# LEDRing.net
KiCad netlist of a schematic drawn in EAGLE
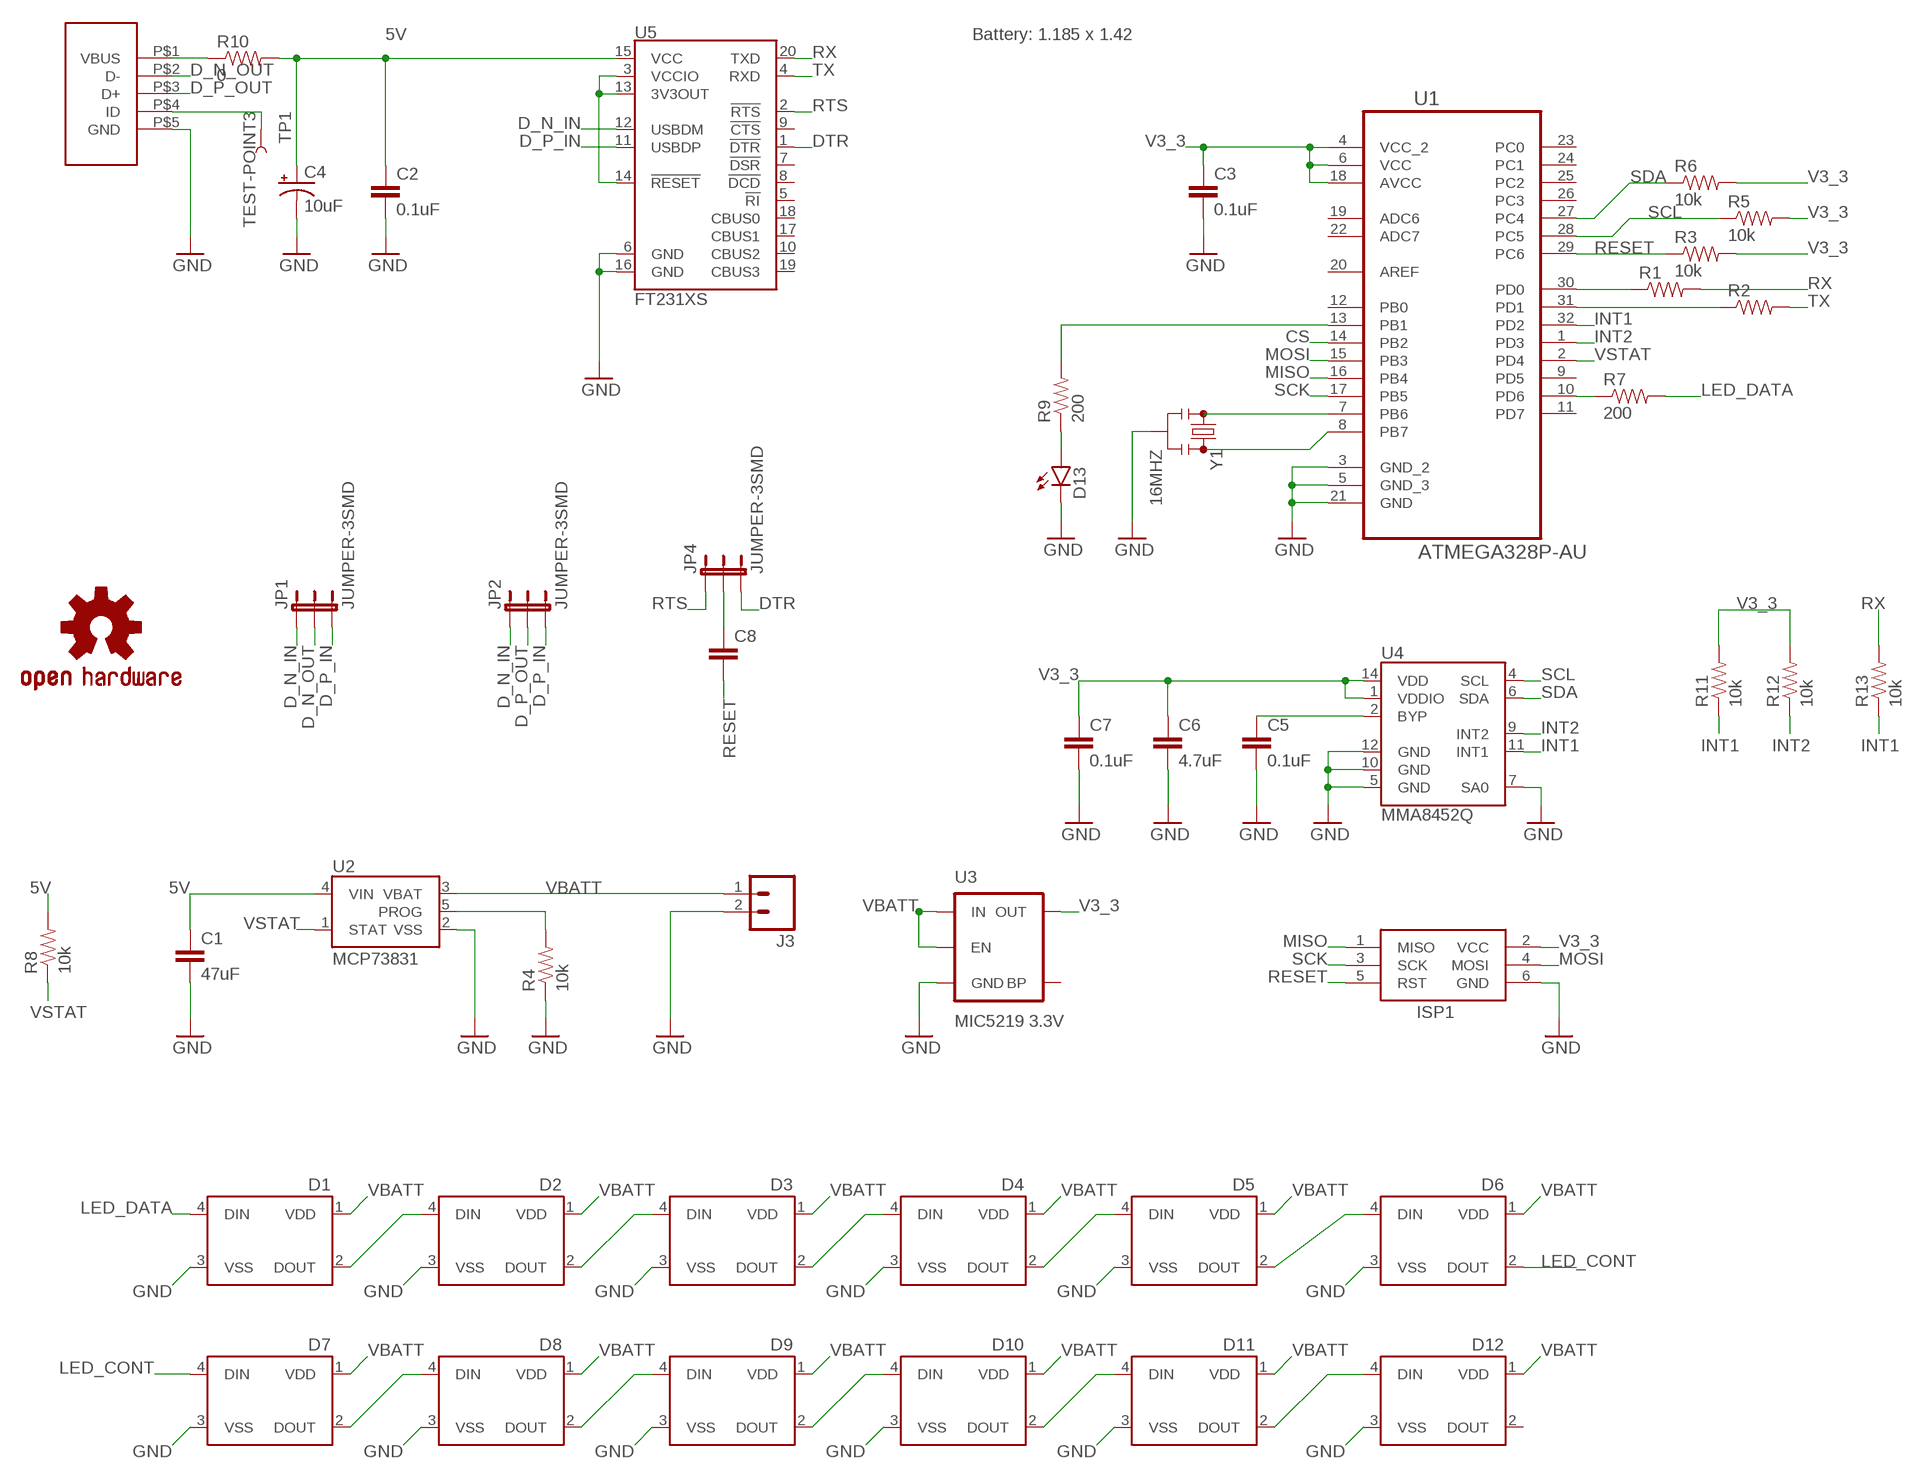
[diagram p0: schematic, sheet 1, part 1 of 2]
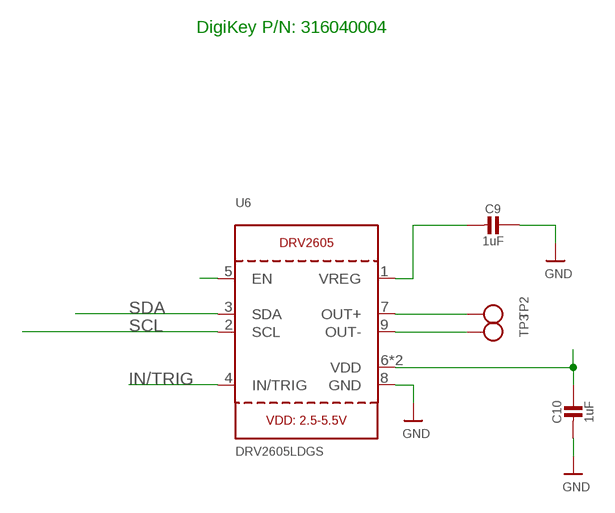
[diagram p1: schematic, sheet 1, part 2 of 2]

(export (version "E")
  (design (tool "Eeschema 10.0.6"))
  (components
    (comp (ref "C1")
      (value "47uF")
      (footprint "eagle-import:0603-CAP")
      (libsource (lib "eagle-import") (part "CAP0603-CAP"))
    )
    (comp (ref "C2")
      (value "0.1uF")
      (footprint "eagle-import:0603-CAP")
      (libsource (lib "eagle-import") (part "CAP0603-CAP"))
    )
    (comp (ref "C3")
      (value "0.1uF")
      (footprint "eagle-import:0603-CAP")
      (libsource (lib "eagle-import") (part "CAP0603-CAP"))
    )
    (comp (ref "C4")
      (value "10uF")
      (footprint "eagle-import:0603-POL")
      (libsource (lib "eagle-import") (part "10UF-6.3V-20%(0603)(TANT){dblquote}"))
    )
    (comp (ref "C5")
      (value "0.1uF")
      (footprint "eagle-import:0603-CAP")
      (libsource (lib "eagle-import") (part "CAP0603-CAP"))
    )
    (comp (ref "C6")
      (value "4.7uF")
      (footprint "eagle-import:0603-CAP")
      (libsource (lib "eagle-import") (part "CAP0603-CAP"))
    )
    (comp (ref "C7")
      (value "0.1uF")
      (footprint "eagle-import:0603-CAP")
      (libsource (lib "eagle-import") (part "CAP0603-CAP"))
    )
    (comp (ref "C8")
      (value "CAP0603-CAP")
      (footprint "eagle-import:0603-CAP")
      (libsource (lib "eagle-import") (part "CAP0603-CAP"))
    )
    (comp (ref "C9")
      (value "1uF")
      (footprint "eagle-import:0805-NO")
      (libsource (lib "eagle-import") (part "CAP_CERAMIC0805-NOOUTLINE"))
    )
    (comp (ref "C10")
      (value "1uF")
      (footprint "eagle-import:0805-NO")
      (libsource (lib "eagle-import") (part "CAP_CERAMIC0805-NOOUTLINE"))
    )
    (comp (ref "D1")
      (value "WS2812B")
      (footprint "eagle-import:WS2812B")
      (libsource (lib "eagle-import") (part "WS2812B"))
    )
    (comp (ref "D2")
      (value "WS2812B")
      (footprint "eagle-import:WS2812B")
      (libsource (lib "eagle-import") (part "WS2812B"))
    )
    (comp (ref "D3")
      (value "WS2812B")
      (footprint "eagle-import:WS2812B")
      (libsource (lib "eagle-import") (part "WS2812B"))
    )
    (comp (ref "D4")
      (value "WS2812B")
      (footprint "eagle-import:WS2812B")
      (libsource (lib "eagle-import") (part "WS2812B"))
    )
    (comp (ref "D5")
      (value "WS2812B")
      (footprint "eagle-import:WS2812B")
      (libsource (lib "eagle-import") (part "WS2812B"))
    )
    (comp (ref "D6")
      (value "WS2812B")
      (footprint "eagle-import:WS2812B")
      (libsource (lib "eagle-import") (part "WS2812B"))
    )
    (comp (ref "D7")
      (value "WS2812B")
      (footprint "eagle-import:WS2812B")
      (libsource (lib "eagle-import") (part "WS2812B"))
    )
    (comp (ref "D8")
      (value "WS2812B")
      (footprint "eagle-import:WS2812B")
      (libsource (lib "eagle-import") (part "WS2812B"))
    )
    (comp (ref "D9")
      (value "WS2812B")
      (footprint "eagle-import:WS2812B")
      (libsource (lib "eagle-import") (part "WS2812B"))
    )
    (comp (ref "D10")
      (value "WS2812B")
      (footprint "eagle-import:WS2812B")
      (libsource (lib "eagle-import") (part "WS2812B"))
    )
    (comp (ref "D11")
      (value "WS2812B")
      (footprint "eagle-import:WS2812B")
      (libsource (lib "eagle-import") (part "WS2812B"))
    )
    (comp (ref "D12")
      (value "WS2812B")
      (footprint "eagle-import:WS2812B")
      (libsource (lib "eagle-import") (part "WS2812B"))
    )
    (comp (ref "D13")
      (value "LED0603")
      (footprint "eagle-import:LED-0603")
      (libsource (lib "eagle-import") (part "LED0603"))
    )
    (comp (ref "ISP1")
      (value "AVRISP-BOX")
      (footprint "eagle-import:AVRISP-BOX")
      (libsource (lib "eagle-import") (part "AVRISP-BOX"))
    )
    (comp (ref "J3")
      (value "M02PTH")
      (footprint "eagle-import:1X02")
      (libsource (lib "eagle-import") (part "M02PTH"))
    )
    (comp (ref "JP1")
      (value "JUMPER-3SMD")
      (footprint "eagle-import:SJ_3")
      (libsource (lib "eagle-import") (part "JUMPER-3SMD"))
    )
    (comp (ref "JP2")
      (value "JUMPER-3SMD")
      (footprint "eagle-import:SJ_3")
      (libsource (lib "eagle-import") (part "JUMPER-3SMD"))
    )
    (comp (ref "JP4")
      (value "JUMPER-3SMD")
      (footprint "eagle-import:SJ_3")
      (libsource (lib "eagle-import") (part "JUMPER-3SMD"))
    )
    (comp (ref "LOGO1")
      (value "OSHW-LOGOMINI")
      (footprint "eagle-import:OSHW-LOGO-MINI")
      (libsource (lib "eagle-import") (part "OSHW-LOGOMINI"))
    )
    (comp (ref "R1")
      (value "RESISTOR0603-RES")
      (footprint "eagle-import:0603-RES")
      (libsource (lib "eagle-import") (part "RESISTOR0603-RES"))
    )
    (comp (ref "R2")
      (value "RESISTOR0603-RES")
      (footprint "eagle-import:0603-RES")
      (libsource (lib "eagle-import") (part "RESISTOR0603-RES"))
    )
    (comp (ref "R3")
      (value "10k")
      (footprint "eagle-import:0603-RES")
      (libsource (lib "eagle-import") (part "RESISTOR0603-RES"))
    )
    (comp (ref "R4")
      (value "10k")
      (footprint "eagle-import:0603-RES")
      (libsource (lib "eagle-import") (part "RESISTOR0603-RES"))
    )
    (comp (ref "R5")
      (value "10k")
      (footprint "eagle-import:0603-RES")
      (libsource (lib "eagle-import") (part "RESISTOR0603-RES"))
    )
    (comp (ref "R6")
      (value "10k")
      (footprint "eagle-import:0603-RES")
      (libsource (lib "eagle-import") (part "RESISTOR0603-RES"))
    )
    (comp (ref "R7")
      (value "200")
      (footprint "eagle-import:0603-RES")
      (libsource (lib "eagle-import") (part "RESISTOR0603-RES"))
    )
    (comp (ref "R8")
      (value "10k")
      (footprint "eagle-import:0603-RES")
      (libsource (lib "eagle-import") (part "RESISTOR0603-RES"))
    )
    (comp (ref "R9")
      (value "200")
      (footprint "eagle-import:0603-RES")
      (libsource (lib "eagle-import") (part "RESISTOR0603-RES"))
    )
    (comp (ref "R10")
      (value "0")
      (footprint "eagle-import:0603-RES")
      (libsource (lib "eagle-import") (part "RESISTOR0603-RES"))
    )
    (comp (ref "R11")
      (value "10k")
      (footprint "eagle-import:0603-RES")
      (libsource (lib "eagle-import") (part "RESISTOR0603-RES"))
    )
    (comp (ref "R12")
      (value "10k")
      (footprint "eagle-import:0603-RES")
      (libsource (lib "eagle-import") (part "RESISTOR0603-RES"))
    )
    (comp (ref "R13")
      (value "10k")
      (footprint "eagle-import:0603-RES")
      (libsource (lib "eagle-import") (part "RESISTOR0603-RES"))
    )
    (comp (ref "TP1")
      (value "TEST-POINT3")
      (footprint "eagle-import:PAD.03X.03")
      (libsource (lib "eagle-import") (part "TEST-POINT3"))
    )
    (comp (ref "TP2")
      (value "TESTPOINTPAD2MM")
      (footprint "eagle-import:TESTPOINT_PAD_2MM")
      (libsource (lib "eagle-import") (part "TESTPOINTPAD2MM"))
    )
    (comp (ref "TP3")
      (value "TESTPOINTPAD2MM")
      (footprint "eagle-import:TESTPOINT_PAD_2MM")
      (libsource (lib "eagle-import") (part "TESTPOINTPAD2MM"))
    )
    (comp (ref "U$1")
      (value "TE_USB_A121025CT")
      (footprint "eagle-import:TE_USB_A121025CT")
      (libsource (lib "eagle-import") (part "TE_USB_A121025CT"))
    )
    (comp (ref "U1")
      (value "ATMEGA328P-AU")
      (footprint "eagle-import:QFP80P900X900X120-32N")
      (libsource (lib "eagle-import") (part "ATMEGA328P-AU"))
    )
    (comp (ref "U2")
      (value "MCP73831")
      (footprint "eagle-import:SOT23-5")
      (libsource (lib "eagle-import") (part "MCP73831"))
    )
    (comp (ref "U3")
      (value "MIC5219 3.3V")
      (footprint "eagle-import:SOT23-5")
      (libsource (lib "eagle-import") (part "V_REG_MIC52193.3V"))
    )
    (comp (ref "U4")
      (value "MMA8452Q")
      (footprint "eagle-import:QFN-16_0.5MM")
      (libsource (lib "eagle-import") (part "MMA8452Q"))
    )
    (comp (ref "U5")
      (value "FT231XS")
      (footprint "eagle-import:SSOP20_L")
      (libsource (lib "eagle-import") (part "FT231XS"))
    )
    (comp (ref "U6")
      (value "DRV2605LDGS")
      (footprint "eagle-import:PSOP10")
      (libsource (lib "eagle-import") (part "DRV2605_SOP"))
    )
    (comp (ref "Y1")
      (value "16MHZ")
      (footprint "eagle-import:RESONATOR-SMD")
      (libsource (lib "eagle-import") (part "RESONATOR16MHZ"))
    )
  )
  (nets
    (net (code "1") (name "/5V") (class "Default")
      (node (ref "C1") (pin "1") (pinfunction "1_1") (pintype "passive"))
      (node (ref "C2") (pin "1") (pinfunction "1_1") (pintype "passive"))
      (node (ref "C4") (pin "A") (pinfunction "+_A") (pintype "passive"))
      (node (ref "R10") (pin "2") (pinfunction "2_2") (pintype "passive"))
      (node (ref "R8") (pin "2") (pinfunction "2_2") (pintype "passive"))
      (node (ref "U2") (pin "4") (pinfunction "VIN_4") (pintype "power_in"))
      (node (ref "U5") (pin "15") (pinfunction "VCC_15") (pintype "bidirectional"))
    )
    (net (code "2") (name "/CS") (class "Default")
      (node (ref "U1") (pin "14") (pinfunction "PB2_14") (pintype "bidirectional"))
    )
    (net (code "3") (name "/DTR") (class "Default")
      (node (ref "JP4") (pin "3") (pinfunction "3_3") (pintype "passive"))
      (node (ref "U5") (pin "1") (pinfunction "~{DTR}_1") (pintype "bidirectional"))
    )
    (net (code "4") (name "/D_N_IN") (class "Default")
      (node (ref "JP1") (pin "1") (pinfunction "1_1") (pintype "passive"))
      (node (ref "JP2") (pin "1") (pinfunction "1_1") (pintype "passive"))
      (node (ref "U5") (pin "12") (pinfunction "USBDM_12") (pintype "bidirectional"))
    )
    (net (code "5") (name "/D_N_OUT") (class "Default")
      (node (ref "JP1") (pin "2") (pinfunction "2_2") (pintype "passive"))
      (node (ref "U$1") (pin "P$2") (pinfunction "D-_P$2") (pintype "bidirectional"))
    )
    (net (code "6") (name "/D_P_IN") (class "Default")
      (node (ref "JP1") (pin "3") (pinfunction "3_3") (pintype "passive"))
      (node (ref "JP2") (pin "3") (pinfunction "3_3") (pintype "passive"))
      (node (ref "U5") (pin "11") (pinfunction "USBDP_11") (pintype "bidirectional"))
    )
    (net (code "7") (name "/D_P_OUT") (class "Default")
      (node (ref "JP2") (pin "2") (pinfunction "2_2") (pintype "passive"))
      (node (ref "U$1") (pin "P$3") (pinfunction "D+_P$3") (pintype "bidirectional"))
    )
    (net (code "8") (name "/INT1") (class "Default")
      (node (ref "R11") (pin "1") (pinfunction "1_1") (pintype "passive"))
      (node (ref "R13") (pin "1") (pinfunction "1_1") (pintype "passive"))
      (node (ref "U1") (pin "32") (pinfunction "PD2_32") (pintype "bidirectional"))
      (node (ref "U4") (pin "11") (pinfunction "INT1_11") (pintype "bidirectional"))
    )
    (net (code "9") (name "/INT2") (class "Default")
      (node (ref "R12") (pin "1") (pinfunction "1_1") (pintype "passive"))
      (node (ref "U1") (pin "1") (pinfunction "PD3_1") (pintype "bidirectional"))
      (node (ref "U4") (pin "9") (pinfunction "INT2_9") (pintype "bidirectional"))
    )
    (net (code "10") (name "/IN{slash}TRIG") (class "Default")
      (node (ref "U6") (pin "4") (pinfunction "IN/TRIG_4") (pintype "input"))
    )
    (net (code "11") (name "/LED_CONT") (class "Default")
      (node (ref "D6") (pin "2") (pinfunction "DOUT_2") (pintype "output"))
      (node (ref "D7") (pin "4") (pinfunction "DIN_4") (pintype "input"))
    )
    (net (code "12") (name "/LED_DATA") (class "Default")
      (node (ref "D1") (pin "4") (pinfunction "DIN_4") (pintype "input"))
      (node (ref "R7") (pin "2") (pinfunction "2_2") (pintype "passive"))
    )
    (net (code "13") (name "/MISO") (class "Default")
      (node (ref "ISP1") (pin "1") (pinfunction "MISO_1") (pintype "input"))
      (node (ref "U1") (pin "16") (pinfunction "PB4_16") (pintype "bidirectional"))
    )
    (net (code "14") (name "/MOSI") (class "Default")
      (node (ref "ISP1") (pin "4") (pinfunction "MOSI_4") (pintype "output"))
      (node (ref "U1") (pin "15") (pinfunction "PB3_15") (pintype "bidirectional"))
    )
    (net (code "15") (name "/RESET") (class "Default")
      (node (ref "C8") (pin "2") (pinfunction "2_2") (pintype "passive"))
      (node (ref "ISP1") (pin "5") (pinfunction "RST_5") (pintype "output"))
      (node (ref "R3") (pin "1") (pinfunction "1_1") (pintype "passive"))
      (node (ref "U1") (pin "29") (pinfunction "PC6_29") (pintype "bidirectional"))
    )
    (net (code "16") (name "/RTS") (class "Default")
      (node (ref "JP4") (pin "1") (pinfunction "1_1") (pintype "passive"))
      (node (ref "U5") (pin "2") (pinfunction "~{RTS}_2") (pintype "bidirectional"))
    )
    (net (code "17") (name "/RX") (class "Default")
      (node (ref "R1") (pin "2") (pinfunction "2_2") (pintype "passive"))
      (node (ref "R13") (pin "2") (pinfunction "2_2") (pintype "passive"))
      (node (ref "U5") (pin "20") (pinfunction "TXD_20") (pintype "bidirectional"))
    )
    (net (code "18") (name "/SCK") (class "Default")
      (node (ref "ISP1") (pin "3") (pinfunction "SCK_3") (pintype "output"))
      (node (ref "U1") (pin "17") (pinfunction "PB5_17") (pintype "bidirectional"))
    )
    (net (code "19") (name "/SCL") (class "Default")
      (node (ref "R5") (pin "1") (pinfunction "1_1") (pintype "passive"))
      (node (ref "U1") (pin "28") (pinfunction "PC5_28") (pintype "bidirectional"))
      (node (ref "U4") (pin "4") (pinfunction "SCL_4") (pintype "bidirectional"))
      (node (ref "U6") (pin "2") (pinfunction "SCL_2") (pintype "input"))
    )
    (net (code "20") (name "/SDA") (class "Default")
      (node (ref "R6") (pin "1") (pinfunction "1_1") (pintype "passive"))
      (node (ref "U1") (pin "27") (pinfunction "PC4_27") (pintype "bidirectional"))
      (node (ref "U4") (pin "6") (pinfunction "SDA_6") (pintype "bidirectional"))
      (node (ref "U6") (pin "3") (pinfunction "SDA_3") (pintype "bidirectional"))
    )
    (net (code "21") (name "/TX") (class "Default")
      (node (ref "R2") (pin "2") (pinfunction "2_2") (pintype "passive"))
      (node (ref "U5") (pin "4") (pinfunction "RXD_4") (pintype "bidirectional"))
    )
    (net (code "22") (name "/V3_3") (class "Default")
      (node (ref "C3") (pin "1") (pinfunction "1_1") (pintype "passive"))
      (node (ref "C6") (pin "1") (pinfunction "1_1") (pintype "passive"))
      (node (ref "C7") (pin "1") (pinfunction "1_1") (pintype "passive"))
      (node (ref "ISP1") (pin "2") (pinfunction "VCC_2") (pintype "power_in"))
      (node (ref "R11") (pin "2") (pinfunction "2_2") (pintype "passive"))
      (node (ref "R12") (pin "2") (pinfunction "2_2") (pintype "passive"))
      (node (ref "R3") (pin "2") (pinfunction "2_2") (pintype "passive"))
      (node (ref "R5") (pin "2") (pinfunction "2_2") (pintype "passive"))
      (node (ref "R6") (pin "2") (pinfunction "2_2") (pintype "passive"))
      (node (ref "U1") (pin "18") (pinfunction "AVCC_18") (pintype "power_in"))
      (node (ref "U1") (pin "4") (pinfunction "VCC_2_4") (pintype "power_in"))
      (node (ref "U1") (pin "6") (pinfunction "VCC_6") (pintype "power_in"))
      (node (ref "U3") (pin "5") (pinfunction "OUT_5") (pintype "passive"))
      (node (ref "U4") (pin "1") (pinfunction "VDDIO_1") (pintype "bidirectional"))
      (node (ref "U4") (pin "14") (pinfunction "VDD_14") (pintype "bidirectional"))
    )
    (net (code "23") (name "/VBATT") (class "Default")
      (node (ref "D1") (pin "1") (pinfunction "VDD_1") (pintype "power_in"))
      (node (ref "D10") (pin "1") (pinfunction "VDD_1") (pintype "power_in"))
      (node (ref "D11") (pin "1") (pinfunction "VDD_1") (pintype "power_in"))
      (node (ref "D12") (pin "1") (pinfunction "VDD_1") (pintype "power_in"))
      (node (ref "D2") (pin "1") (pinfunction "VDD_1") (pintype "power_in"))
      (node (ref "D3") (pin "1") (pinfunction "VDD_1") (pintype "power_in"))
      (node (ref "D4") (pin "1") (pinfunction "VDD_1") (pintype "power_in"))
      (node (ref "D5") (pin "1") (pinfunction "VDD_1") (pintype "power_in"))
      (node (ref "D6") (pin "1") (pinfunction "VDD_1") (pintype "power_in"))
      (node (ref "D7") (pin "1") (pinfunction "VDD_1") (pintype "power_in"))
      (node (ref "D8") (pin "1") (pinfunction "VDD_1") (pintype "power_in"))
      (node (ref "D9") (pin "1") (pinfunction "VDD_1") (pintype "power_in"))
      (node (ref "J3") (pin "1") (pinfunction "1_1") (pintype "passive"))
      (node (ref "U2") (pin "3") (pinfunction "VBAT_3") (pintype "power_in"))
      (node (ref "U3") (pin "1") (pinfunction "IN_1") (pintype "input"))
      (node (ref "U3") (pin "3") (pinfunction "EN_3") (pintype "input"))
    )
    (net (code "24") (name "/VSTAT") (class "Default")
      (node (ref "R8") (pin "1") (pinfunction "1_1") (pintype "passive"))
      (node (ref "U1") (pin "2") (pinfunction "PD4_2") (pintype "bidirectional"))
      (node (ref "U2") (pin "1") (pinfunction "STAT_1") (pintype "output"))
    )
    (net (code "25") (name "GND") (class "Default")
      (node (ref "C1") (pin "2") (pinfunction "2_2") (pintype "passive"))
      (node (ref "C10") (pin "2") (pinfunction "2_2") (pintype "passive"))
      (node (ref "C2") (pin "2") (pinfunction "2_2") (pintype "passive"))
      (node (ref "C3") (pin "2") (pinfunction "2_2") (pintype "passive"))
      (node (ref "C4") (pin "K") (pinfunction "-_K") (pintype "passive"))
      (node (ref "C5") (pin "2") (pinfunction "2_2") (pintype "passive"))
      (node (ref "C6") (pin "2") (pinfunction "2_2") (pintype "passive"))
      (node (ref "C7") (pin "2") (pinfunction "2_2") (pintype "passive"))
      (node (ref "C9") (pin "1") (pinfunction "1_1") (pintype "passive"))
      (node (ref "D1") (pin "3") (pinfunction "VSS_3") (pintype "power_in"))
      (node (ref "D10") (pin "3") (pinfunction "VSS_3") (pintype "power_in"))
      (node (ref "D11") (pin "3") (pinfunction "VSS_3") (pintype "power_in"))
      (node (ref "D12") (pin "3") (pinfunction "VSS_3") (pintype "power_in"))
      (node (ref "D13") (pin "C") (pinfunction "C_C") (pintype "passive"))
      (node (ref "D2") (pin "3") (pinfunction "VSS_3") (pintype "power_in"))
      (node (ref "D3") (pin "3") (pinfunction "VSS_3") (pintype "power_in"))
      (node (ref "D4") (pin "3") (pinfunction "VSS_3") (pintype "power_in"))
      (node (ref "D5") (pin "3") (pinfunction "VSS_3") (pintype "power_in"))
      (node (ref "D6") (pin "3") (pinfunction "VSS_3") (pintype "power_in"))
      (node (ref "D7") (pin "3") (pinfunction "VSS_3") (pintype "power_in"))
      (node (ref "D8") (pin "3") (pinfunction "VSS_3") (pintype "power_in"))
      (node (ref "D9") (pin "3") (pinfunction "VSS_3") (pintype "power_in"))
      (node (ref "ISP1") (pin "6") (pinfunction "GND_6") (pintype "power_in"))
      (node (ref "J3") (pin "2") (pinfunction "2_2") (pintype "passive"))
      (node (ref "R4") (pin "1") (pinfunction "1_1") (pintype "passive"))
      (node (ref "U$1") (pin "P$5") (pinfunction "GND_P$5") (pintype "bidirectional"))
      (node (ref "U1") (pin "21") (pinfunction "GND_21") (pintype "passive"))
      (node (ref "U1") (pin "3") (pinfunction "GND_2_3") (pintype "passive"))
      (node (ref "U1") (pin "5") (pinfunction "GND_3_5") (pintype "passive"))
      (node (ref "U2") (pin "2") (pinfunction "VSS_2") (pintype "power_in"))
      (node (ref "U3") (pin "2") (pinfunction "GND_2") (pintype "input"))
      (node (ref "U4") (pin "10") (pinfunction "GND_10") (pintype "bidirectional"))
      (node (ref "U4") (pin "12") (pinfunction "GND_12") (pintype "bidirectional"))
      (node (ref "U4") (pin "5") (pinfunction "GND_5") (pintype "bidirectional"))
      (node (ref "U4") (pin "7") (pinfunction "SA0_7") (pintype "bidirectional"))
      (node (ref "U5") (pin "16") (pinfunction "GND_16") (pintype "bidirectional"))
      (node (ref "U5") (pin "6") (pinfunction "GND_6") (pintype "bidirectional"))
      (node (ref "U6") (pin "8") (pinfunction "GND_8") (pintype "power_in"))
      (node (ref "Y1") (pin "2") (pinfunction "2_2") (pintype "passive"))
    )
    (net (code "26") (name "Net-(C8-Pad1)") (class "Default")
      (node (ref "C8") (pin "1") (pinfunction "1_1") (pintype "passive"))
      (node (ref "JP4") (pin "2") (pinfunction "2_2") (pintype "passive"))
    )
    (net (code "27") (name "Net-(C10-Pad1)") (class "Default")
      (node (ref "C10") (pin "1") (pinfunction "1_1") (pintype "passive"))
      (node (ref "U6") (pin "10") (pinfunction "VDD_10") (pintype "power_in"))
      (node (ref "U6") (pin "6") (pinfunction "VDD_6") (pintype "power_in"))
    )
    (net (code "28") (name "Net-(D1-DOUT)") (class "Default")
      (node (ref "D1") (pin "2") (pinfunction "DOUT_2") (pintype "output"))
      (node (ref "D2") (pin "4") (pinfunction "DIN_4") (pintype "input"))
    )
    (net (code "29") (name "Net-(D2-DOUT)") (class "Default")
      (node (ref "D2") (pin "2") (pinfunction "DOUT_2") (pintype "output"))
      (node (ref "D3") (pin "4") (pinfunction "DIN_4") (pintype "input"))
    )
    (net (code "30") (name "Net-(D3-DOUT)") (class "Default")
      (node (ref "D3") (pin "2") (pinfunction "DOUT_2") (pintype "output"))
      (node (ref "D4") (pin "4") (pinfunction "DIN_4") (pintype "input"))
    )
    (net (code "31") (name "Net-(D4-DOUT)") (class "Default")
      (node (ref "D4") (pin "2") (pinfunction "DOUT_2") (pintype "output"))
      (node (ref "D5") (pin "4") (pinfunction "DIN_4") (pintype "input"))
    )
    (net (code "32") (name "Net-(D5-DOUT)") (class "Default")
      (node (ref "D5") (pin "2") (pinfunction "DOUT_2") (pintype "output"))
      (node (ref "D6") (pin "4") (pinfunction "DIN_4") (pintype "input"))
    )
    (net (code "33") (name "Net-(D7-DOUT)") (class "Default")
      (node (ref "D7") (pin "2") (pinfunction "DOUT_2") (pintype "output"))
      (node (ref "D8") (pin "4") (pinfunction "DIN_4") (pintype "input"))
    )
    (net (code "34") (name "Net-(D8-DOUT)") (class "Default")
      (node (ref "D8") (pin "2") (pinfunction "DOUT_2") (pintype "output"))
      (node (ref "D9") (pin "4") (pinfunction "DIN_4") (pintype "input"))
    )
    (net (code "35") (name "Net-(D10-DIN)") (class "Default")
      (node (ref "D10") (pin "4") (pinfunction "DIN_4") (pintype "input"))
      (node (ref "D9") (pin "2") (pinfunction "DOUT_2") (pintype "output"))
    )
    (net (code "36") (name "Net-(D10-DOUT)") (class "Default")
      (node (ref "D10") (pin "2") (pinfunction "DOUT_2") (pintype "output"))
      (node (ref "D11") (pin "4") (pinfunction "DIN_4") (pintype "input"))
    )
    (net (code "37") (name "Net-(D11-DOUT)") (class "Default")
      (node (ref "D11") (pin "2") (pinfunction "DOUT_2") (pintype "output"))
      (node (ref "D12") (pin "4") (pinfunction "DIN_4") (pintype "input"))
    )
    (net (code "38") (name "Net-(D13-PadA)") (class "Default")
      (node (ref "D13") (pin "A") (pinfunction "A_A") (pintype "passive"))
      (node (ref "R9") (pin "1") (pinfunction "1_1") (pintype "passive"))
    )
    (net (code "39") (name "Net-(TP1-1)") (class "Default")
      (node (ref "TP1") (pin "P$1") (pinfunction "1_P$1") (pintype "bidirectional"))
      (node (ref "U$1") (pin "P$4") (pinfunction "ID_P$4") (pintype "bidirectional"))
    )
    (net (code "40") (name "Net-(U$1-VBUS)") (class "Default")
      (node (ref "R10") (pin "1") (pinfunction "1_1") (pintype "passive"))
      (node (ref "U$1") (pin "P$1") (pinfunction "VBUS_P$1") (pintype "bidirectional"))
    )
    (net (code "41") (name "Net-(U1-PB1)") (class "Default")
      (node (ref "R9") (pin "2") (pinfunction "2_2") (pintype "passive"))
      (node (ref "U1") (pin "13") (pinfunction "PB1_13") (pintype "bidirectional"))
    )
    (net (code "42") (name "Net-(U1-PB6)") (class "Default")
      (node (ref "U1") (pin "7") (pinfunction "PB6_7") (pintype "bidirectional"))
      (node (ref "Y1") (pin "1") (pinfunction "1_1") (pintype "passive"))
    )
    (net (code "43") (name "Net-(U1-PB7)") (class "Default")
      (node (ref "U1") (pin "8") (pinfunction "PB7_8") (pintype "bidirectional"))
      (node (ref "Y1") (pin "3") (pinfunction "3_3") (pintype "passive"))
    )
    (net (code "44") (name "Net-(U1-PD0)") (class "Default")
      (node (ref "R1") (pin "1") (pinfunction "1_1") (pintype "passive"))
      (node (ref "U1") (pin "30") (pinfunction "PD0_30") (pintype "bidirectional"))
    )
    (net (code "45") (name "Net-(U1-PD1)") (class "Default")
      (node (ref "R2") (pin "1") (pinfunction "1_1") (pintype "passive"))
      (node (ref "U1") (pin "31") (pinfunction "PD1_31") (pintype "bidirectional"))
    )
    (net (code "46") (name "Net-(U1-PD6)") (class "Default")
      (node (ref "R7") (pin "1") (pinfunction "1_1") (pintype "passive"))
      (node (ref "U1") (pin "10") (pinfunction "PD6_10") (pintype "bidirectional"))
    )
    (net (code "47") (name "Net-(U2-PROG)") (class "Default")
      (node (ref "R4") (pin "2") (pinfunction "2_2") (pintype "passive"))
      (node (ref "U2") (pin "5") (pinfunction "PROG_5") (pintype "input"))
    )
    (net (code "48") (name "Net-(U4-BYP)") (class "Default")
      (node (ref "C5") (pin "1") (pinfunction "1_1") (pintype "passive"))
      (node (ref "U4") (pin "2") (pinfunction "BYP_2") (pintype "bidirectional"))
    )
    (net (code "49") (name "Net-(U5-3V3OUT)") (class "Default")
      (node (ref "U5") (pin "13") (pinfunction "3V3OUT_13") (pintype "bidirectional"))
      (node (ref "U5") (pin "14") (pinfunction "~{RESET}_14") (pintype "bidirectional"))
      (node (ref "U5") (pin "3") (pinfunction "VCCIO_3") (pintype "bidirectional"))
    )
    (net (code "50") (name "Net-(U6-OUT+)") (class "Default")
      (node (ref "TP2") (pin "P$1") (pinfunction "P$1_P$1") (pintype "bidirectional"))
      (node (ref "U6") (pin "7") (pinfunction "OUT+_7") (pintype "output"))
    )
    (net (code "51") (name "Net-(U6-OUT-)") (class "Default")
      (node (ref "TP3") (pin "P$1") (pinfunction "P$1_P$1") (pintype "bidirectional"))
      (node (ref "U6") (pin "9") (pinfunction "OUT-_9") (pintype "output"))
    )
    (net (code "52") (name "Net-(U6-VREG)") (class "Default")
      (node (ref "C9") (pin "2") (pinfunction "2_2") (pintype "passive"))
      (node (ref "U6") (pin "1") (pinfunction "VREG_1") (pintype "output"))
    )
    (net (code "53") (name "unconnected-(D12-DOUT-Pad2)") (class "Default")
      (node (ref "D12") (pin "2") (pinfunction "DOUT_2") (pintype "output"))
    )
    (net (code "54") (name "unconnected-(U1-ADC6-Pad19)") (class "Default")
      (node (ref "U1") (pin "19") (pinfunction "ADC6_19") (pintype "input"))
    )
    (net (code "55") (name "unconnected-(U1-ADC7-Pad22)") (class "Default")
      (node (ref "U1") (pin "22") (pinfunction "ADC7_22") (pintype "input"))
    )
    (net (code "56") (name "unconnected-(U1-AREF-Pad20)") (class "Default")
      (node (ref "U1") (pin "20") (pinfunction "AREF_20") (pintype "input"))
    )
    (net (code "57") (name "unconnected-(U1-PB0-Pad12)") (class "Default")
      (node (ref "U1") (pin "12") (pinfunction "PB0_12") (pintype "bidirectional"))
    )
    (net (code "58") (name "unconnected-(U1-PC0-Pad23)") (class "Default")
      (node (ref "U1") (pin "23") (pinfunction "PC0_23") (pintype "bidirectional"))
    )
    (net (code "59") (name "unconnected-(U1-PC1-Pad24)") (class "Default")
      (node (ref "U1") (pin "24") (pinfunction "PC1_24") (pintype "bidirectional"))
    )
    (net (code "60") (name "unconnected-(U1-PC2-Pad25)") (class "Default")
      (node (ref "U1") (pin "25") (pinfunction "PC2_25") (pintype "bidirectional"))
    )
    (net (code "61") (name "unconnected-(U1-PC3-Pad26)") (class "Default")
      (node (ref "U1") (pin "26") (pinfunction "PC3_26") (pintype "bidirectional"))
    )
    (net (code "62") (name "unconnected-(U1-PD5-Pad9)") (class "Default")
      (node (ref "U1") (pin "9") (pinfunction "PD5_9") (pintype "bidirectional"))
    )
    (net (code "63") (name "unconnected-(U1-PD7-Pad11)") (class "Default")
      (node (ref "U1") (pin "11") (pinfunction "PD7_11") (pintype "bidirectional"))
    )
    (net (code "64") (name "unconnected-(U3-BP-Pad4)") (class "Default")
      (node (ref "U3") (pin "4") (pinfunction "BP_4") (pintype "input"))
    )
    (net (code "65") (name "unconnected-(U5-CBUS0-Pad18)") (class "Default")
      (node (ref "U5") (pin "18") (pinfunction "CBUS0_18") (pintype "bidirectional"))
    )
    (net (code "66") (name "unconnected-(U5-CBUS1-Pad17)") (class "Default")
      (node (ref "U5") (pin "17") (pinfunction "CBUS1_17") (pintype "bidirectional"))
    )
    (net (code "67") (name "unconnected-(U5-CBUS2-Pad10)") (class "Default")
      (node (ref "U5") (pin "10") (pinfunction "CBUS2_10") (pintype "bidirectional"))
    )
    (net (code "68") (name "unconnected-(U5-CBUS3-Pad19)") (class "Default")
      (node (ref "U5") (pin "19") (pinfunction "CBUS3_19") (pintype "bidirectional"))
    )
    (net (code "69") (name "unconnected-(U5-~{CTS}-Pad9)") (class "Default")
      (node (ref "U5") (pin "9") (pinfunction "~{CTS}_9") (pintype "bidirectional"))
    )
    (net (code "70") (name "unconnected-(U5-~{DCD}-Pad8)") (class "Default")
      (node (ref "U5") (pin "8") (pinfunction "~{DCD}_8") (pintype "bidirectional"))
    )
    (net (code "71") (name "unconnected-(U5-~{DSR}-Pad7)") (class "Default")
      (node (ref "U5") (pin "7") (pinfunction "~{DSR}_7") (pintype "bidirectional"))
    )
    (net (code "72") (name "unconnected-(U5-~{RI}-Pad5)") (class "Default")
      (node (ref "U5") (pin "5") (pinfunction "~{RI}_5") (pintype "bidirectional"))
    )
    (net (code "73") (name "unconnected-(U6-EN-Pad5)") (class "Default")
      (node (ref "U6") (pin "5") (pinfunction "EN_5") (pintype "input"))
    )
  )
)
